# charging_block_v3.net
KiCad netlist of a schematic drawn in EAGLE
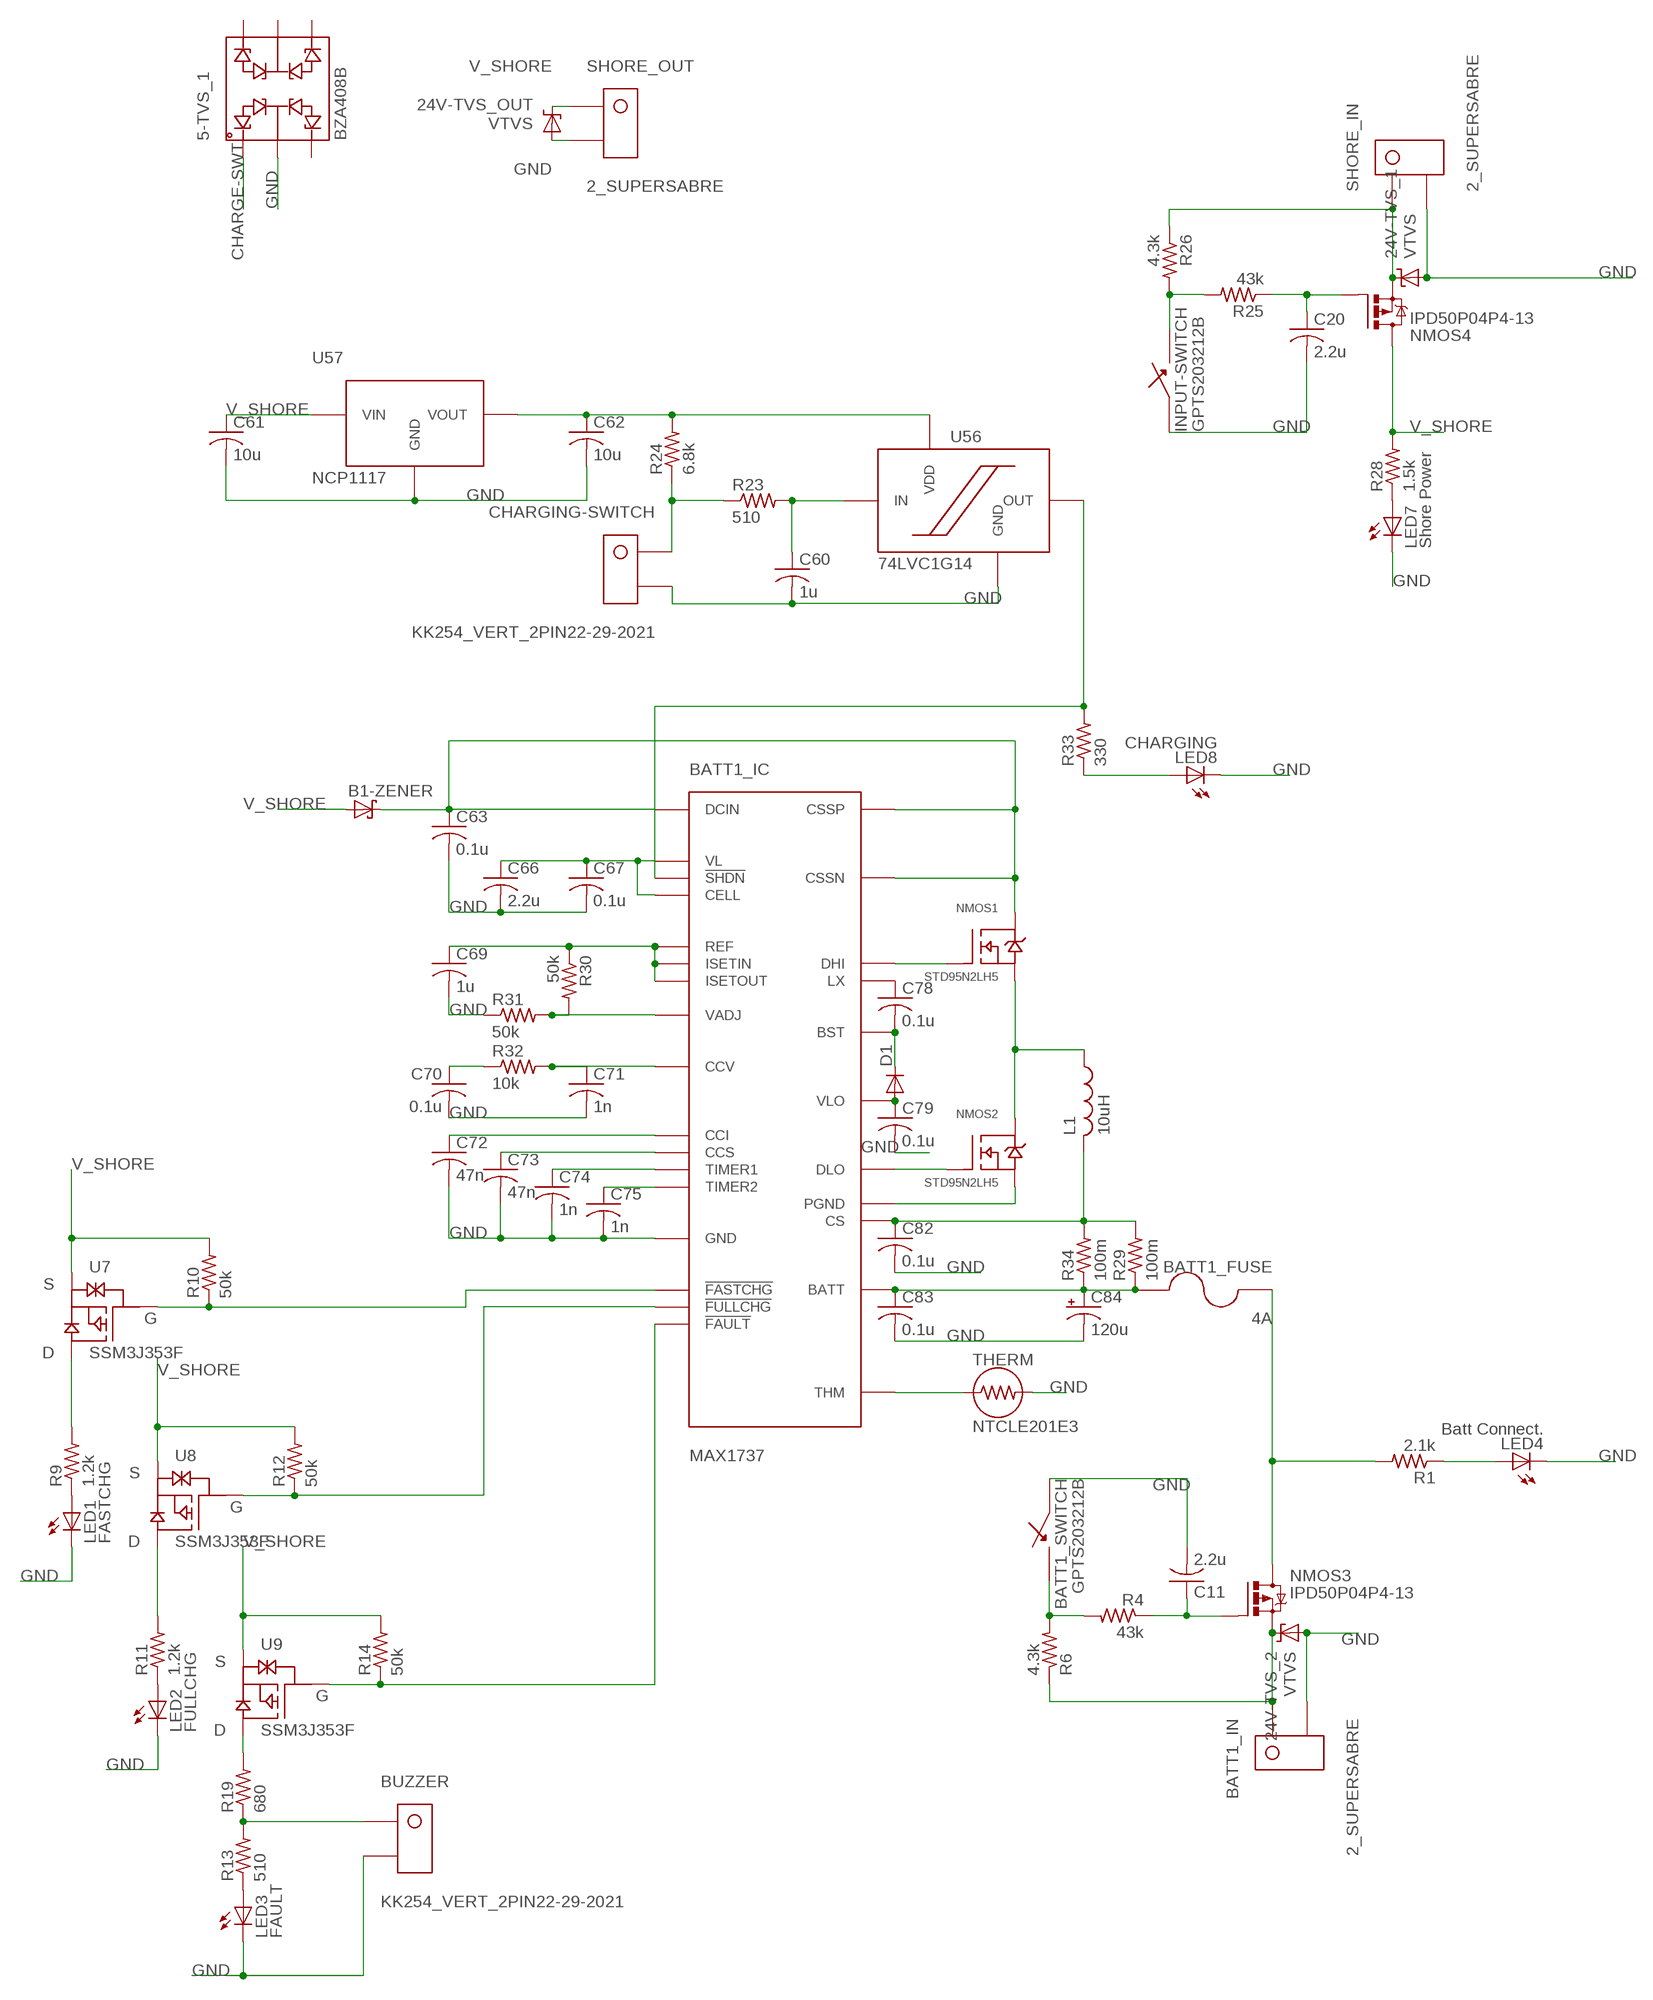
[diagram p0: schematic, sheet 1]

(export (version "E")
  (design (tool "Eeschema 10.0.6"))
  (components
    (comp (ref "5-TVS_1")
      (value "BZA408B")
      (footprint "eagle-import:SOT457")
      (libsource (lib "eagle-import") (part "BZA408B"))
    )
    (comp (ref "24V-TVS_1")
      (value "VTVS")
      (footprint "eagle-import:DO-219AB")
      (libsource (lib "eagle-import") (part "VTVS"))
    )
    (comp (ref "24V-TVS_2")
      (value "VTVS")
      (footprint "eagle-import:DO-219AB")
      (libsource (lib "eagle-import") (part "VTVS"))
    )
    (comp (ref "24V-TVS_OUT")
      (value "VTVS")
      (footprint "eagle-import:DO-219AB")
      (libsource (lib "eagle-import") (part "VTVS"))
    )
    (comp (ref "B1-ZENER")
      (value "SCHOTTKY-DIODESOD-106")
      (footprint "eagle-import:SOD106-R")
      (libsource (lib "eagle-import") (part "SCHOTTKY-DIODESOD-106"))
    )
    (comp (ref "BATT1_FUSE")
      (value "4A")
      (footprint "eagle-import:154-OMNI-BLOK")
      (libsource (lib "eagle-import") (part "154-OMNI_BLOK"))
    )
    (comp (ref "BATT1_IC")
      (value "MAX1737")
      (footprint "eagle-import:QSOP28")
      (libsource (lib "eagle-import") (part "MAX1737"))
    )
    (comp (ref "BATT1_IN")
      (value "2_SUPERSABRE")
      (footprint "eagle-import:SUPERSABRE_2CIRCUIT")
      (libsource (lib "eagle-import") (part "2_SUPERSABRE"))
    )
    (comp (ref "BATT1_SWITCH")
      (value "GPTS203212B")
      (footprint "eagle-import:GPTS203211B")
      (libsource (lib "eagle-import") (part "GPTS203212B"))
    )
    (comp (ref "BUZZER")
      (value "KK254_VERT_2PIN22-29-2021")
      (footprint "eagle-import:KK254_VERT_2PIN")
      (libsource (lib "eagle-import") (part "KK254_VERT_2PIN22-29-2021"))
    )
    (comp (ref "C11")
      (value "2.2u")
      (footprint "eagle-import:C0805")
      (libsource (lib "eagle-import") (part "C-USC0805"))
    )
    (comp (ref "C20")
      (value "2.2u")
      (footprint "eagle-import:C0805")
      (libsource (lib "eagle-import") (part "C-USC0805"))
    )
    (comp (ref "C60")
      (value "1u")
      (footprint "eagle-import:C0805")
      (libsource (lib "eagle-import") (part "C-USC0805"))
    )
    (comp (ref "C61")
      (value "10u")
      (footprint "eagle-import:C0805")
      (libsource (lib "eagle-import") (part "C-USC0805"))
    )
    (comp (ref "C62")
      (value "10u")
      (footprint "eagle-import:C0805")
      (libsource (lib "eagle-import") (part "C-USC0805"))
    )
    (comp (ref "C63")
      (value "0.1u")
      (footprint "eagle-import:C0805")
      (libsource (lib "eagle-import") (part "C-USC0805"))
    )
    (comp (ref "C66")
      (value "2.2u")
      (footprint "eagle-import:C0805")
      (libsource (lib "eagle-import") (part "C-USC0805"))
    )
    (comp (ref "C67")
      (value "0.1u")
      (footprint "eagle-import:C0805")
      (libsource (lib "eagle-import") (part "C-USC0805"))
    )
    (comp (ref "C69")
      (value "1u")
      (footprint "eagle-import:C0805")
      (libsource (lib "eagle-import") (part "C-USC0805"))
    )
    (comp (ref "C70")
      (value "0.1u")
      (footprint "eagle-import:C0805")
      (libsource (lib "eagle-import") (part "C-USC0805"))
    )
    (comp (ref "C71")
      (value "1n")
      (footprint "eagle-import:C0805")
      (libsource (lib "eagle-import") (part "C-USC0805"))
    )
    (comp (ref "C72")
      (value "47n")
      (footprint "eagle-import:C0805")
      (libsource (lib "eagle-import") (part "C-USC0805"))
    )
    (comp (ref "C73")
      (value "47n")
      (footprint "eagle-import:C0805")
      (libsource (lib "eagle-import") (part "C-USC0805"))
    )
    (comp (ref "C74")
      (value "1n")
      (footprint "eagle-import:C0805")
      (libsource (lib "eagle-import") (part "C-USC0805"))
    )
    (comp (ref "C75")
      (value "1n")
      (footprint "eagle-import:C0805")
      (libsource (lib "eagle-import") (part "C-USC0805"))
    )
    (comp (ref "C78")
      (value "0.1u")
      (footprint "eagle-import:C0805")
      (libsource (lib "eagle-import") (part "C-USC0805"))
    )
    (comp (ref "C79")
      (value "0.1u")
      (footprint "eagle-import:C0805")
      (libsource (lib "eagle-import") (part "C-USC0805"))
    )
    (comp (ref "C82")
      (value "0.1u")
      (footprint "eagle-import:C0805")
      (libsource (lib "eagle-import") (part "C-USC0805"))
    )
    (comp (ref "C83")
      (value "0.1u")
      (footprint "eagle-import:C0805")
      (libsource (lib "eagle-import") (part "C-USC0805"))
    )
    (comp (ref "C84")
      (value "120u")
      (footprint "eagle-import:E3,5-8")
      (libsource (lib "eagle-import") (part "CPOL-USE3.5-8"))
    )
    (comp (ref "CHARGING-SWITCH")
      (value "KK254_VERT_2PIN22-29-2021")
      (footprint "eagle-import:KK254_VERT_2PIN")
      (libsource (lib "eagle-import") (part "KK254_VERT_2PIN22-29-2021"))
    )
    (comp (ref "D1")
      (value "DIODE-SOD123")
      (footprint "eagle-import:SOD123")
      (libsource (lib "eagle-import") (part "DIODE-SOD123"))
    )
    (comp (ref "INPUT-SWITCH")
      (value "GPTS203212B")
      (footprint "eagle-import:GPTS203211B")
      (libsource (lib "eagle-import") (part "GPTS203212B"))
    )
    (comp (ref "L1")
      (value "10uH")
      (footprint "eagle-import:L6100")
      (libsource (lib "eagle-import") (part "L-USL6100"))
    )
    (comp (ref "LED1")
      (value "FASTCHG")
      (footprint "eagle-import:CHIP-LED0805")
      (libsource (lib "eagle-import") (part "LEDCHIP-LED0805"))
    )
    (comp (ref "LED2")
      (value "FULLCHG")
      (footprint "eagle-import:CHIP-LED0805")
      (libsource (lib "eagle-import") (part "LEDCHIP-LED0805"))
    )
    (comp (ref "LED3")
      (value "FAULT")
      (footprint "eagle-import:CHIP-LED0805")
      (libsource (lib "eagle-import") (part "LEDCHIP-LED0805"))
    )
    (comp (ref "LED4")
      (value "Batt Connect.")
      (footprint "eagle-import:CHIP-LED0805")
      (libsource (lib "eagle-import") (part "LEDCHIP-LED0805"))
    )
    (comp (ref "LED7")
      (value "Shore Power")
      (footprint "eagle-import:CHIP-LED0805")
      (libsource (lib "eagle-import") (part "LEDCHIP-LED0805"))
    )
    (comp (ref "LED8")
      (value "CHARGING")
      (footprint "eagle-import:CHIP-LED0805")
      (libsource (lib "eagle-import") (part "LEDCHIP-LED0805"))
    )
    (comp (ref "NMOS1")
      (value "STD95N2LH5")
      (footprint "eagle-import:DPAK")
      (libsource (lib "eagle-import") (part "STD95N2LH5"))
    )
    (comp (ref "NMOS2")
      (value "STD95N2LH5")
      (footprint "eagle-import:DPAK")
      (libsource (lib "eagle-import") (part "STD95N2LH5"))
    )
    (comp (ref "NMOS3")
      (value "IPD50P04P4-13")
      (footprint "eagle-import:TO252-3")
      (libsource (lib "eagle-import") (part "IPD50P04P4-13"))
    )
    (comp (ref "NMOS4")
      (value "IPD50P04P4-13")
      (footprint "eagle-import:TO252-3")
      (libsource (lib "eagle-import") (part "IPD50P04P4-13"))
    )
    (comp (ref "R1")
      (value "2.1k")
      (footprint "eagle-import:R0805")
      (libsource (lib "eagle-import") (part "R-US_R0805"))
    )
    (comp (ref "R4")
      (value "43k")
      (footprint "eagle-import:R0805")
      (libsource (lib "eagle-import") (part "R-US_R0805"))
    )
    (comp (ref "R6")
      (value "4.3k")
      (footprint "eagle-import:R0805")
      (libsource (lib "eagle-import") (part "R-US_R0805"))
    )
    (comp (ref "R9")
      (value "1.2k")
      (footprint "eagle-import:R0805")
      (libsource (lib "eagle-import") (part "R-US_R0805"))
    )
    (comp (ref "R10")
      (value "50k")
      (footprint "eagle-import:R0805")
      (libsource (lib "eagle-import") (part "R-US_R0805"))
    )
    (comp (ref "R11")
      (value "1.2k")
      (footprint "eagle-import:R0805")
      (libsource (lib "eagle-import") (part "R-US_R0805"))
    )
    (comp (ref "R12")
      (value "50k")
      (footprint "eagle-import:R0805")
      (libsource (lib "eagle-import") (part "R-US_R0805"))
    )
    (comp (ref "R13")
      (value "510")
      (footprint "eagle-import:R0805")
      (libsource (lib "eagle-import") (part "R-US_R0805"))
    )
    (comp (ref "R14")
      (value "50k")
      (footprint "eagle-import:R0805")
      (libsource (lib "eagle-import") (part "R-US_R0805"))
    )
    (comp (ref "R19")
      (value "680")
      (footprint "eagle-import:R0805")
      (libsource (lib "eagle-import") (part "R-US_R0805"))
    )
    (comp (ref "R23")
      (value "510")
      (footprint "eagle-import:R0805")
      (libsource (lib "eagle-import") (part "R-US_R0805"))
    )
    (comp (ref "R24")
      (value "6.8k")
      (footprint "eagle-import:R0805")
      (libsource (lib "eagle-import") (part "R-US_R0805"))
    )
    (comp (ref "R25")
      (value "43k")
      (footprint "eagle-import:R0805")
      (libsource (lib "eagle-import") (part "R-US_R0805"))
    )
    (comp (ref "R26")
      (value "4.3k")
      (footprint "eagle-import:R0805")
      (libsource (lib "eagle-import") (part "R-US_R0805"))
    )
    (comp (ref "R28")
      (value "1.5k")
      (footprint "eagle-import:R0805")
      (libsource (lib "eagle-import") (part "R-US_R0805"))
    )
    (comp (ref "R29")
      (value "100m")
      (footprint "eagle-import:R2512")
      (libsource (lib "eagle-import") (part "R-US_R2512"))
    )
    (comp (ref "R30")
      (value "50k")
      (footprint "eagle-import:R0805")
      (libsource (lib "eagle-import") (part "R-US_R0805"))
    )
    (comp (ref "R31")
      (value "50k")
      (footprint "eagle-import:R0805")
      (libsource (lib "eagle-import") (part "R-US_R0805"))
    )
    (comp (ref "R32")
      (value "10k")
      (footprint "eagle-import:R0805")
      (libsource (lib "eagle-import") (part "R-US_R0805"))
    )
    (comp (ref "R33")
      (value "330")
      (footprint "eagle-import:R0805")
      (libsource (lib "eagle-import") (part "R-US_R0805"))
    )
    (comp (ref "R34")
      (value "100m")
      (footprint "eagle-import:R2512")
      (libsource (lib "eagle-import") (part "R-US_R2512"))
    )
    (comp (ref "SHORE_IN")
      (value "2_SUPERSABRE")
      (footprint "eagle-import:SUPERSABRE_2CIRCUIT")
      (libsource (lib "eagle-import") (part "2_SUPERSABRE"))
    )
    (comp (ref "SHORE_OUT")
      (value "2_SUPERSABRE")
      (footprint "eagle-import:SUPERSABRE_2CIRCUIT")
      (libsource (lib "eagle-import") (part "2_SUPERSABRE"))
    )
    (comp (ref "THERM")
      (value "NTCLE201E3")
      (footprint "eagle-import:2-0.3MM-LEADS")
      (libsource (lib "eagle-import") (part "NTCLE201E3"))
    )
    (comp (ref "U7")
      (value "SSM3J353F")
      (footprint "eagle-import:SOT-346-3_S-MINI")
      (libsource (lib "eagle-import") (part "SSM3J353F"))
    )
    (comp (ref "U8")
      (value "SSM3J353F")
      (footprint "eagle-import:SOT-346-3_S-MINI")
      (libsource (lib "eagle-import") (part "SSM3J353F"))
    )
    (comp (ref "U9")
      (value "SSM3J353F")
      (footprint "eagle-import:SOT-346-3_S-MINI")
      (libsource (lib "eagle-import") (part "SSM3J353F"))
    )
    (comp (ref "U56")
      (value "74LVC1G14")
      (footprint "eagle-import:TSSOP5")
      (libsource (lib "eagle-import") (part "74LVC1G14"))
    )
    (comp (ref "U57")
      (value "NCP1117")
      (footprint "eagle-import:SOT-223")
      (libsource (lib "eagle-import") (part "NCP1117"))
    )
  )
  (nets
    (net (code "1") (name "/CHARGE-SWT") (class "Default")
      (node (ref "5-TVS_1") (pin "P$1") (pinfunction "P$1_P$1") (pintype "bidirectional"))
      (node (ref "CHARGING-SWITCH") (pin "P$1") (pinfunction "P$1_P$1") (pintype "bidirectional"))
      (node (ref "R23") (pin "1") (pinfunction "1_1") (pintype "passive"))
      (node (ref "R24") (pin "1") (pinfunction "1_1") (pintype "passive"))
    )
    (net (code "2") (name "/GND") (class "Default")
      (node (ref "24V-TVS_1") (pin "P$1") (pinfunction "A_P$1") (pintype "passive"))
      (node (ref "24V-TVS_2") (pin "P$1") (pinfunction "A_P$1") (pintype "passive"))
      (node (ref "24V-TVS_OUT") (pin "P$1") (pinfunction "A_P$1") (pintype "passive"))
      (node (ref "5-TVS_1") (pin "P$2") (pinfunction "P$2_P$2") (pintype "bidirectional"))
      (node (ref "BATT1_IC") (pin "6") (pinfunction "GND_6") (pintype "bidirectional"))
      (node (ref "BATT1_IN") (pin "P$2") (pinfunction "P$2_P$2") (pintype "bidirectional"))
      (node (ref "BATT1_SWITCH") (pin "P$1") (pinfunction "P$1_P$1") (pintype "bidirectional"))
      (node (ref "BUZZER") (pin "P$2") (pinfunction "P$2_P$2") (pintype "bidirectional"))
      (node (ref "C11") (pin "2") (pinfunction "2_2") (pintype "passive"))
      (node (ref "C20") (pin "2") (pinfunction "2_2") (pintype "passive"))
      (node (ref "C60") (pin "2") (pinfunction "2_2") (pintype "passive"))
      (node (ref "C61") (pin "2") (pinfunction "2_2") (pintype "passive"))
      (node (ref "C62") (pin "2") (pinfunction "2_2") (pintype "passive"))
      (node (ref "C63") (pin "2") (pinfunction "2_2") (pintype "passive"))
      (node (ref "C66") (pin "2") (pinfunction "2_2") (pintype "passive"))
      (node (ref "C67") (pin "2") (pinfunction "2_2") (pintype "passive"))
      (node (ref "C69") (pin "2") (pinfunction "2_2") (pintype "passive"))
      (node (ref "C70") (pin "2") (pinfunction "2_2") (pintype "passive"))
      (node (ref "C71") (pin "2") (pinfunction "2_2") (pintype "passive"))
      (node (ref "C72") (pin "2") (pinfunction "2_2") (pintype "passive"))
      (node (ref "C73") (pin "2") (pinfunction "2_2") (pintype "passive"))
      (node (ref "C74") (pin "2") (pinfunction "2_2") (pintype "passive"))
      (node (ref "C75") (pin "2") (pinfunction "2_2") (pintype "passive"))
      (node (ref "C79") (pin "2") (pinfunction "2_2") (pintype "passive"))
      (node (ref "C82") (pin "2") (pinfunction "2_2") (pintype "passive"))
      (node (ref "C83") (pin "2") (pinfunction "2_2") (pintype "passive"))
      (node (ref "C84") (pin "-") (pinfunction "-_-") (pintype "passive"))
      (node (ref "CHARGING-SWITCH") (pin "P$2") (pinfunction "P$2_P$2") (pintype "bidirectional"))
      (node (ref "INPUT-SWITCH") (pin "P$1") (pinfunction "P$1_P$1") (pintype "bidirectional"))
      (node (ref "LED1") (pin "C") (pinfunction "C_C") (pintype "passive"))
      (node (ref "LED2") (pin "C") (pinfunction "C_C") (pintype "passive"))
      (node (ref "LED3") (pin "C") (pinfunction "C_C") (pintype "passive"))
      (node (ref "LED4") (pin "C") (pinfunction "C_C") (pintype "passive"))
      (node (ref "LED7") (pin "C") (pinfunction "C_C") (pintype "passive"))
      (node (ref "LED8") (pin "C") (pinfunction "C_C") (pintype "passive"))
      (node (ref "R31") (pin "1") (pinfunction "1_1") (pintype "passive"))
      (node (ref "SHORE_IN") (pin "P$2") (pinfunction "P$2_P$2") (pintype "bidirectional"))
      (node (ref "SHORE_OUT") (pin "P$2") (pinfunction "P$2_P$2") (pintype "bidirectional"))
      (node (ref "THERM") (pin "P$2") (pinfunction "2_P$2") (pintype "passive"))
      (node (ref "U56") (pin "P$3") (pinfunction "GND_P$3") (pintype "bidirectional"))
      (node (ref "U57") (pin "P$1") (pinfunction "GND_P$1") (pintype "bidirectional"))
    )
    (net (code "3") (name "/V_SHORE") (class "Default")
      (node (ref "24V-TVS_OUT") (pin "P$2") (pinfunction "C_P$2") (pintype "passive"))
      (node (ref "B1-ZENER") (pin "A") (pinfunction "A_A") (pintype "passive"))
      (node (ref "C61") (pin "1") (pinfunction "1_1") (pintype "passive"))
      (node (ref "NMOS4") (pin "3") (pinfunction "S_3") (pintype "passive"))
      (node (ref "R10") (pin "2") (pinfunction "2_2") (pintype "passive"))
      (node (ref "R12") (pin "2") (pinfunction "2_2") (pintype "passive"))
      (node (ref "R14") (pin "2") (pinfunction "2_2") (pintype "passive"))
      (node (ref "R28") (pin "2") (pinfunction "2_2") (pintype "passive"))
      (node (ref "SHORE_OUT") (pin "P$1") (pinfunction "P$1_P$1") (pintype "bidirectional"))
      (node (ref "U57") (pin "P$3") (pinfunction "VIN_P$3") (pintype "bidirectional"))
      (node (ref "U7") (pin "P$3") (pinfunction "S_P$3") (pintype "bidirectional"))
      (node (ref "U8") (pin "P$3") (pinfunction "S_P$3") (pintype "bidirectional"))
      (node (ref "U9") (pin "P$3") (pinfunction "S_P$3") (pintype "bidirectional"))
    )
    (net (code "4") (name "Net-(24V-TVS_1-C)") (class "Default")
      (node (ref "24V-TVS_1") (pin "P$2") (pinfunction "C_P$2") (pintype "passive"))
      (node (ref "NMOS4") (pin "TAB") (pinfunction "D_TAB") (pintype "passive"))
      (node (ref "R26") (pin "1") (pinfunction "1_1") (pintype "passive"))
      (node (ref "SHORE_IN") (pin "P$1") (pinfunction "P$1_P$1") (pintype "bidirectional"))
    )
    (net (code "5") (name "Net-(24V-TVS_2-C)") (class "Default")
      (node (ref "24V-TVS_2") (pin "P$2") (pinfunction "C_P$2") (pintype "passive"))
      (node (ref "BATT1_IN") (pin "P$1") (pinfunction "P$1_P$1") (pintype "bidirectional"))
      (node (ref "NMOS3") (pin "TAB") (pinfunction "D_TAB") (pintype "passive"))
      (node (ref "R6") (pin "1") (pinfunction "1_1") (pintype "passive"))
    )
    (net (code "6") (name "Net-(BATT1_IC-BATT)") (class "Default")
      (node (ref "BATT1_FUSE") (pin "P$2") (pinfunction "P$2_P$2") (pintype "bidirectional"))
      (node (ref "BATT1_IC") (pin "7") (pinfunction "BATT_7") (pintype "bidirectional"))
      (node (ref "C83") (pin "1") (pinfunction "1_1") (pintype "passive"))
      (node (ref "C84") (pin "+") (pinfunction "+_+") (pintype "passive"))
      (node (ref "R29") (pin "1") (pinfunction "1_1") (pintype "passive"))
      (node (ref "R34") (pin "1") (pinfunction "1_1") (pintype "passive"))
    )
    (net (code "7") (name "Net-(BATT1_IC-BST)") (class "Default")
      (node (ref "BATT1_IC") (pin "23") (pinfunction "BST_23") (pintype "bidirectional"))
      (node (ref "C78") (pin "2") (pinfunction "2_2") (pintype "passive"))
      (node (ref "D1") (pin "C") (pinfunction "C_C") (pintype "passive"))
    )
    (net (code "8") (name "Net-(BATT1_IC-CCI)") (class "Default")
      (node (ref "BATT1_IC") (pin "11") (pinfunction "CCI_11") (pintype "bidirectional"))
      (node (ref "C72") (pin "1") (pinfunction "1_1") (pintype "passive"))
    )
    (net (code "9") (name "Net-(BATT1_IC-CCS)") (class "Default")
      (node (ref "BATT1_IC") (pin "10") (pinfunction "CCS_10") (pintype "bidirectional"))
      (node (ref "C73") (pin "1") (pinfunction "1_1") (pintype "passive"))
    )
    (net (code "10") (name "Net-(BATT1_IC-CCV)") (class "Default")
      (node (ref "BATT1_IC") (pin "9") (pinfunction "CCV_9") (pintype "bidirectional"))
      (node (ref "C71") (pin "1") (pinfunction "1_1") (pintype "passive"))
      (node (ref "R32") (pin "2") (pinfunction "2_2") (pintype "passive"))
    )
    (net (code "11") (name "Net-(BATT1_IC-CELL)") (class "Default")
      (node (ref "BATT1_IC") (pin "1") (pinfunction "VL_1") (pintype "bidirectional"))
      (node (ref "BATT1_IC") (pin "12") (pinfunction "CELL_12") (pintype "bidirectional"))
      (node (ref "C66") (pin "1") (pinfunction "1_1") (pintype "passive"))
      (node (ref "C67") (pin "1") (pinfunction "1_1") (pintype "passive"))
    )
    (net (code "12") (name "Net-(BATT1_IC-CS)") (class "Default")
      (node (ref "BATT1_IC") (pin "19") (pinfunction "CS_19") (pintype "bidirectional"))
      (node (ref "C82") (pin "1") (pinfunction "1_1") (pintype "passive"))
      (node (ref "L1") (pin "P$2") (pinfunction "2_P$2") (pintype "passive"))
      (node (ref "R29") (pin "2") (pinfunction "2_2") (pintype "passive"))
      (node (ref "R34") (pin "2") (pinfunction "2_2") (pintype "passive"))
    )
    (net (code "13") (name "Net-(BATT1_IC-CSSN)") (class "Default")
      (node (ref "B1-ZENER") (pin "C") (pinfunction "C_C") (pintype "passive"))
      (node (ref "BATT1_IC") (pin "26") (pinfunction "CSSN_26") (pintype "bidirectional"))
      (node (ref "BATT1_IC") (pin "27") (pinfunction "CSSP_27") (pintype "bidirectional"))
      (node (ref "BATT1_IC") (pin "28") (pinfunction "DCIN_28") (pintype "bidirectional"))
      (node (ref "C63") (pin "1") (pinfunction "1_1") (pintype "passive"))
      (node (ref "NMOS1") (pin "TAB") (pinfunction "D_TAB") (pintype "bidirectional"))
    )
    (net (code "14") (name "Net-(BATT1_IC-DHI)") (class "Default")
      (node (ref "BATT1_IC") (pin "25") (pinfunction "DHI_25") (pintype "bidirectional"))
      (node (ref "NMOS1") (pin "1") (pinfunction "G_1") (pintype "bidirectional"))
    )
    (net (code "15") (name "Net-(BATT1_IC-DLO)") (class "Default")
      (node (ref "BATT1_IC") (pin "21") (pinfunction "DLO_21") (pintype "bidirectional"))
      (node (ref "NMOS2") (pin "1") (pinfunction "G_1") (pintype "bidirectional"))
    )
    (net (code "16") (name "Net-(BATT1_IC-ISETIN)") (class "Default")
      (node (ref "BATT1_IC") (pin "2") (pinfunction "ISETIN_2") (pintype "bidirectional"))
      (node (ref "BATT1_IC") (pin "3") (pinfunction "ISETOUT_3") (pintype "bidirectional"))
      (node (ref "BATT1_IC") (pin "5") (pinfunction "REF_5") (pintype "bidirectional"))
      (node (ref "C69") (pin "1") (pinfunction "1_1") (pintype "passive"))
      (node (ref "R30") (pin "1") (pinfunction "1_1") (pintype "passive"))
    )
    (net (code "17") (name "Net-(BATT1_IC-LX)") (class "Default")
      (node (ref "BATT1_IC") (pin "24") (pinfunction "LX_24") (pintype "bidirectional"))
      (node (ref "C78") (pin "1") (pinfunction "1_1") (pintype "passive"))
    )
    (net (code "18") (name "Net-(BATT1_IC-PGND)") (class "Default")
      (node (ref "BATT1_IC") (pin "20") (pinfunction "PGND_20") (pintype "bidirectional"))
      (node (ref "NMOS2") (pin "3") (pinfunction "S_3") (pintype "bidirectional"))
    )
    (net (code "19") (name "Net-(BATT1_IC-THM)") (class "Default")
      (node (ref "BATT1_IC") (pin "4") (pinfunction "THM_4") (pintype "bidirectional"))
      (node (ref "THERM") (pin "P$1") (pinfunction "1_P$1") (pintype "passive"))
    )
    (net (code "20") (name "Net-(BATT1_IC-TIMER1)") (class "Default")
      (node (ref "BATT1_IC") (pin "13") (pinfunction "TIMER1_13") (pintype "bidirectional"))
      (node (ref "C74") (pin "1") (pinfunction "1_1") (pintype "passive"))
    )
    (net (code "21") (name "Net-(BATT1_IC-TIMER2)") (class "Default")
      (node (ref "BATT1_IC") (pin "14") (pinfunction "TIMER2_14") (pintype "bidirectional"))
      (node (ref "C75") (pin "1") (pinfunction "1_1") (pintype "passive"))
    )
    (net (code "22") (name "Net-(BATT1_IC-VADJ)") (class "Default")
      (node (ref "BATT1_IC") (pin "8") (pinfunction "VADJ_8") (pintype "bidirectional"))
      (node (ref "R30") (pin "2") (pinfunction "2_2") (pintype "passive"))
      (node (ref "R31") (pin "2") (pinfunction "2_2") (pintype "passive"))
    )
    (net (code "23") (name "Net-(BATT1_IC-VLO)") (class "Default")
      (node (ref "BATT1_IC") (pin "22") (pinfunction "VLO_22") (pintype "bidirectional"))
      (node (ref "C79") (pin "1") (pinfunction "1_1") (pintype "passive"))
      (node (ref "D1") (pin "A") (pinfunction "A_A") (pintype "passive"))
    )
    (net (code "24") (name "Net-(BATT1_IC-~{FASTCHG})") (class "Default")
      (node (ref "BATT1_IC") (pin "16") (pinfunction "~{FASTCHG}_16") (pintype "bidirectional"))
      (node (ref "R10") (pin "1") (pinfunction "1_1") (pintype "passive"))
      (node (ref "U7") (pin "P$1") (pinfunction "G_P$1") (pintype "bidirectional"))
    )
    (net (code "25") (name "Net-(BATT1_IC-~{FAULT})") (class "Default")
      (node (ref "BATT1_IC") (pin "15") (pinfunction "~{FAULT}_15") (pintype "bidirectional"))
      (node (ref "R14") (pin "1") (pinfunction "1_1") (pintype "passive"))
      (node (ref "U9") (pin "P$1") (pinfunction "G_P$1") (pintype "bidirectional"))
    )
    (net (code "26") (name "Net-(BATT1_IC-~{FULLCHG})") (class "Default")
      (node (ref "BATT1_IC") (pin "17") (pinfunction "~{FULLCHG}_17") (pintype "bidirectional"))
      (node (ref "R12") (pin "1") (pinfunction "1_1") (pintype "passive"))
      (node (ref "U8") (pin "P$1") (pinfunction "G_P$1") (pintype "bidirectional"))
    )
    (net (code "27") (name "Net-(BATT1_IC-~{SHDN})") (class "Default")
      (node (ref "BATT1_IC") (pin "18") (pinfunction "~{SHDN}_18") (pintype "bidirectional"))
      (node (ref "R33") (pin "2") (pinfunction "2_2") (pintype "passive"))
      (node (ref "U56") (pin "P$4") (pinfunction "OUT_P$4") (pintype "bidirectional"))
    )
    (net (code "28") (name "Net-(BATT1_SWITCH-PadP$2)") (class "Default")
      (node (ref "BATT1_SWITCH") (pin "P$2") (pinfunction "P$2_P$2") (pintype "bidirectional"))
      (node (ref "R4") (pin "2") (pinfunction "2_2") (pintype "passive"))
      (node (ref "R6") (pin "2") (pinfunction "2_2") (pintype "passive"))
    )
    (net (code "29") (name "Net-(BUZZER-PadP$1)") (class "Default")
      (node (ref "BUZZER") (pin "P$1") (pinfunction "P$1_P$1") (pintype "bidirectional"))
      (node (ref "R13") (pin "2") (pinfunction "2_2") (pintype "passive"))
      (node (ref "R19") (pin "1") (pinfunction "1_1") (pintype "passive"))
    )
    (net (code "30") (name "Net-(C70-Pad1)") (class "Default")
      (node (ref "C70") (pin "1") (pinfunction "1_1") (pintype "passive"))
      (node (ref "R32") (pin "1") (pinfunction "1_1") (pintype "passive"))
    )
    (net (code "31") (name "Net-(INPUT-SWITCH-PadP$2)") (class "Default")
      (node (ref "INPUT-SWITCH") (pin "P$2") (pinfunction "P$2_P$2") (pintype "bidirectional"))
      (node (ref "R25") (pin "2") (pinfunction "2_2") (pintype "passive"))
      (node (ref "R26") (pin "2") (pinfunction "2_2") (pintype "passive"))
    )
    (net (code "32") (name "Net-(L1-1)") (class "Default")
      (node (ref "L1") (pin "P$1") (pinfunction "1_P$1") (pintype "passive"))
      (node (ref "NMOS1") (pin "3") (pinfunction "S_3") (pintype "bidirectional"))
      (node (ref "NMOS2") (pin "TAB") (pinfunction "D_TAB") (pintype "bidirectional"))
    )
    (net (code "33") (name "Net-(LED1-PadA)") (class "Default")
      (node (ref "LED1") (pin "A") (pinfunction "A_A") (pintype "passive"))
      (node (ref "R9") (pin "1") (pinfunction "1_1") (pintype "passive"))
    )
    (net (code "34") (name "Net-(LED2-PadA)") (class "Default")
      (node (ref "LED2") (pin "A") (pinfunction "A_A") (pintype "passive"))
      (node (ref "R11") (pin "1") (pinfunction "1_1") (pintype "passive"))
    )
    (net (code "35") (name "Net-(LED3-PadA)") (class "Default")
      (node (ref "LED3") (pin "A") (pinfunction "A_A") (pintype "passive"))
      (node (ref "R13") (pin "1") (pinfunction "1_1") (pintype "passive"))
    )
    (net (code "36") (name "Net-(LED4-PadA)") (class "Default")
      (node (ref "LED4") (pin "A") (pinfunction "A_A") (pintype "passive"))
      (node (ref "R1") (pin "1") (pinfunction "1_1") (pintype "passive"))
    )
    (net (code "37") (name "Net-(LED7-PadA)") (class "Default")
      (node (ref "LED7") (pin "A") (pinfunction "A_A") (pintype "passive"))
      (node (ref "R28") (pin "1") (pinfunction "1_1") (pintype "passive"))
    )
    (net (code "38") (name "Net-(LED8-PadA)") (class "Default")
      (node (ref "LED8") (pin "A") (pinfunction "A_A") (pintype "passive"))
      (node (ref "R33") (pin "1") (pinfunction "1_1") (pintype "passive"))
    )
    (net (code "39") (name "Net-(NMOS3-G)") (class "Default")
      (node (ref "C11") (pin "1") (pinfunction "1_1") (pintype "passive"))
      (node (ref "NMOS3") (pin "1") (pinfunction "G_1") (pintype "passive"))
      (node (ref "R4") (pin "1") (pinfunction "1_1") (pintype "passive"))
    )
    (net (code "40") (name "Net-(NMOS3-S)") (class "Default")
      (node (ref "BATT1_FUSE") (pin "P$1") (pinfunction "P$1_P$1") (pintype "bidirectional"))
      (node (ref "NMOS3") (pin "3") (pinfunction "S_3") (pintype "passive"))
      (node (ref "R1") (pin "2") (pinfunction "2_2") (pintype "passive"))
    )
    (net (code "41") (name "Net-(NMOS4-G)") (class "Default")
      (node (ref "C20") (pin "1") (pinfunction "1_1") (pintype "passive"))
      (node (ref "NMOS4") (pin "1") (pinfunction "G_1") (pintype "passive"))
      (node (ref "R25") (pin "1") (pinfunction "1_1") (pintype "passive"))
    )
    (net (code "42") (name "Net-(U7-D)") (class "Default")
      (node (ref "R9") (pin "2") (pinfunction "2_2") (pintype "passive"))
      (node (ref "U7") (pin "P$2") (pinfunction "D_P$2") (pintype "bidirectional"))
    )
    (net (code "43") (name "Net-(U8-D)") (class "Default")
      (node (ref "R11") (pin "2") (pinfunction "2_2") (pintype "passive"))
      (node (ref "U8") (pin "P$2") (pinfunction "D_P$2") (pintype "bidirectional"))
    )
    (net (code "44") (name "Net-(U9-D)") (class "Default")
      (node (ref "R19") (pin "2") (pinfunction "2_2") (pintype "passive"))
      (node (ref "U9") (pin "P$2") (pinfunction "D_P$2") (pintype "bidirectional"))
    )
    (net (code "45") (name "Net-(U56-IN)") (class "Default")
      (node (ref "C60") (pin "1") (pinfunction "1_1") (pintype "passive"))
      (node (ref "R23") (pin "2") (pinfunction "2_2") (pintype "passive"))
      (node (ref "U56") (pin "P$2") (pinfunction "IN_P$2") (pintype "bidirectional"))
    )
    (net (code "46") (name "Net-(U56-VDD)") (class "Default")
      (node (ref "C62") (pin "1") (pinfunction "1_1") (pintype "passive"))
      (node (ref "R24") (pin "2") (pinfunction "2_2") (pintype "passive"))
      (node (ref "U56") (pin "P$5") (pinfunction "VDD_P$5") (pintype "bidirectional"))
      (node (ref "U57") (pin "P$2") (pinfunction "VOUT_P$2") (pintype "bidirectional"))
      (node (ref "U57") (pin "P$4") (pinfunction "VOUT_P$4") (pintype "bidirectional"))
    )
    (net (code "47") (name "unconnected-(5-TVS_1-PadP$3)") (class "Default")
      (node (ref "5-TVS_1") (pin "P$3") (pinfunction "P$3_P$3") (pintype "bidirectional"))
    )
    (net (code "48") (name "unconnected-(5-TVS_1-PadP$4)") (class "Default")
      (node (ref "5-TVS_1") (pin "P$4") (pinfunction "P$4_P$4") (pintype "bidirectional"))
    )
    (net (code "49") (name "unconnected-(5-TVS_1-PadP$5)") (class "Default")
      (node (ref "5-TVS_1") (pin "P$5") (pinfunction "P$5_P$5") (pintype "bidirectional"))
    )
    (net (code "50") (name "unconnected-(5-TVS_1-PadP$6)") (class "Default")
      (node (ref "5-TVS_1") (pin "P$6") (pinfunction "P$6_P$6") (pintype "bidirectional"))
    )
  )
)
